# mixer.net
KiCad netlist of a schematic drawn in EAGLE
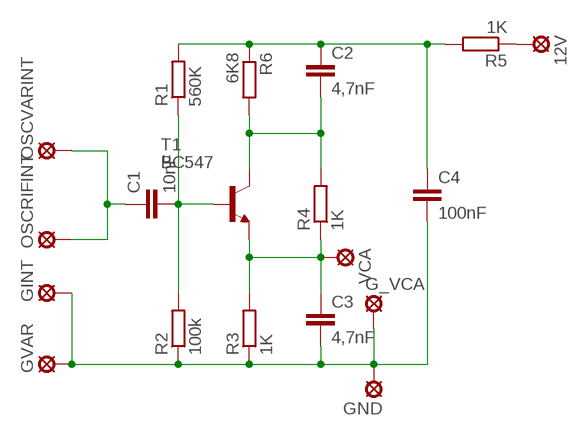
[diagram p0: schematic, sheet 1]

(export (version "E")
  (design (tool "Eeschema 10.0.6"))
  (components
    (comp (ref "12V")
      (value "LSP10")
      (footprint "eagle-import:LSP10")
      (libsource (lib "eagle-import") (part "LSP10"))
    )
    (comp (ref "C1")
      (value "10nF")
      (footprint "eagle-import:C050-025X075")
      (libsource (lib "eagle-import") (part "C-EU050-025X075"))
    )
    (comp (ref "C2")
      (value "4,7nF")
      (footprint "eagle-import:C050-025X075")
      (libsource (lib "eagle-import") (part "C-EU050-025X075"))
    )
    (comp (ref "C3")
      (value "4,7nF")
      (footprint "eagle-import:C050-025X075")
      (libsource (lib "eagle-import") (part "C-EU050-025X075"))
    )
    (comp (ref "C4")
      (value "100nF")
      (footprint "eagle-import:C050-025X075")
      (libsource (lib "eagle-import") (part "C-EU050-025X075"))
    )
    (comp (ref "GINT")
      (value "LSP10")
      (footprint "eagle-import:LSP10")
      (libsource (lib "eagle-import") (part "LSP10"))
    )
    (comp (ref "GND")
      (value "LSP10")
      (footprint "eagle-import:LSP10")
      (libsource (lib "eagle-import") (part "LSP10"))
    )
    (comp (ref "GVAR")
      (value "LSP10")
      (footprint "eagle-import:LSP10")
      (libsource (lib "eagle-import") (part "LSP10"))
    )
    (comp (ref "G_VCA")
      (value "LSP10")
      (footprint "eagle-import:LSP10")
      (libsource (lib "eagle-import") (part "LSP10"))
    )
    (comp (ref "OSCRIFINT")
      (value "LSP10")
      (footprint "eagle-import:LSP10")
      (libsource (lib "eagle-import") (part "LSP10"))
    )
    (comp (ref "OSCVARINT")
      (value "LSP10")
      (footprint "eagle-import:LSP10")
      (libsource (lib "eagle-import") (part "LSP10"))
    )
    (comp (ref "R1")
      (value "560K")
      (footprint "eagle-import:0207_12")
      (libsource (lib "eagle-import") (part "R-EU_0207/12"))
    )
    (comp (ref "R2")
      (value "100k")
      (footprint "eagle-import:0207_12")
      (libsource (lib "eagle-import") (part "R-EU_0207/12"))
    )
    (comp (ref "R3")
      (value "1K")
      (footprint "eagle-import:0207_12")
      (libsource (lib "eagle-import") (part "R-EU_0207/12"))
    )
    (comp (ref "R4")
      (value "1K")
      (footprint "eagle-import:0207_12")
      (libsource (lib "eagle-import") (part "R-EU_0207/12"))
    )
    (comp (ref "R5")
      (value "1K")
      (footprint "eagle-import:0207_12")
      (libsource (lib "eagle-import") (part "R-EU_0207/12"))
    )
    (comp (ref "R6")
      (value "6K8")
      (footprint "eagle-import:0207_12")
      (libsource (lib "eagle-import") (part "R-EU_0207/12"))
    )
    (comp (ref "T1")
      (value "BC547")
      (footprint "eagle-import:TO92")
      (libsource (lib "eagle-import") (part "BC547"))
    )
    (comp (ref "VCA")
      (value "LSP10")
      (footprint "eagle-import:LSP10")
      (libsource (lib "eagle-import") (part "LSP10"))
    )
  )
  (nets
    (net (code "1") (name "Net-(12V-PadMP)") (class "Default")
      (node (ref "12V") (pin "MP") (pinfunction "MP_MP") (pintype "passive"))
      (node (ref "R5") (pin "1") (pinfunction "1_1") (pintype "passive"))
    )
    (net (code "2") (name "Net-(C1-Pad1)") (class "Default")
      (node (ref "C1") (pin "1") (pinfunction "1_1") (pintype "passive"))
      (node (ref "OSCRIFINT") (pin "MP") (pinfunction "MP_MP") (pintype "passive"))
      (node (ref "OSCVARINT") (pin "MP") (pinfunction "MP_MP") (pintype "passive"))
    )
    (net (code "3") (name "Net-(C2-Pad1)") (class "Default")
      (node (ref "C2") (pin "1") (pinfunction "1_1") (pintype "passive"))
      (node (ref "C4") (pin "1") (pinfunction "1_1") (pintype "passive"))
      (node (ref "R1") (pin "2") (pinfunction "2_2") (pintype "passive"))
      (node (ref "R5") (pin "2") (pinfunction "2_2") (pintype "passive"))
      (node (ref "R6") (pin "1") (pinfunction "1_1") (pintype "passive"))
    )
    (net (code "4") (name "Net-(C3-Pad2)") (class "Default")
      (node (ref "C3") (pin "2") (pinfunction "2_2") (pintype "passive"))
      (node (ref "C4") (pin "2") (pinfunction "2_2") (pintype "passive"))
      (node (ref "GINT") (pin "MP") (pinfunction "MP_MP") (pintype "passive"))
      (node (ref "GND") (pin "MP") (pinfunction "MP_MP") (pintype "passive"))
      (node (ref "GVAR") (pin "MP") (pinfunction "MP_MP") (pintype "passive"))
      (node (ref "G_VCA") (pin "MP") (pinfunction "MP_MP") (pintype "passive"))
      (node (ref "R2") (pin "1") (pinfunction "1_1") (pintype "passive"))
      (node (ref "R3") (pin "1") (pinfunction "1_1") (pintype "passive"))
    )
    (net (code "5") (name "Net-(T1-B)") (class "Default")
      (node (ref "C1") (pin "2") (pinfunction "2_2") (pintype "passive"))
      (node (ref "R1") (pin "1") (pinfunction "1_1") (pintype "passive"))
      (node (ref "R2") (pin "2") (pinfunction "2_2") (pintype "passive"))
      (node (ref "T1") (pin "2") (pinfunction "B_2") (pintype "passive"))
    )
    (net (code "6") (name "Net-(T1-C)") (class "Default")
      (node (ref "C2") (pin "2") (pinfunction "2_2") (pintype "passive"))
      (node (ref "R4") (pin "2") (pinfunction "2_2") (pintype "passive"))
      (node (ref "R6") (pin "2") (pinfunction "2_2") (pintype "passive"))
      (node (ref "T1") (pin "3") (pinfunction "C_3") (pintype "passive"))
    )
    (net (code "7") (name "Net-(T1-E)") (class "Default")
      (node (ref "C3") (pin "1") (pinfunction "1_1") (pintype "passive"))
      (node (ref "R3") (pin "2") (pinfunction "2_2") (pintype "passive"))
      (node (ref "R4") (pin "1") (pinfunction "1_1") (pintype "passive"))
      (node (ref "T1") (pin "1") (pinfunction "E_1") (pintype "passive"))
      (node (ref "VCA") (pin "MP") (pinfunction "MP_MP") (pintype "passive"))
    )
  )
)
